# 23_PCIe.net
KiCad netlist of a schematic drawn in Altium Designer
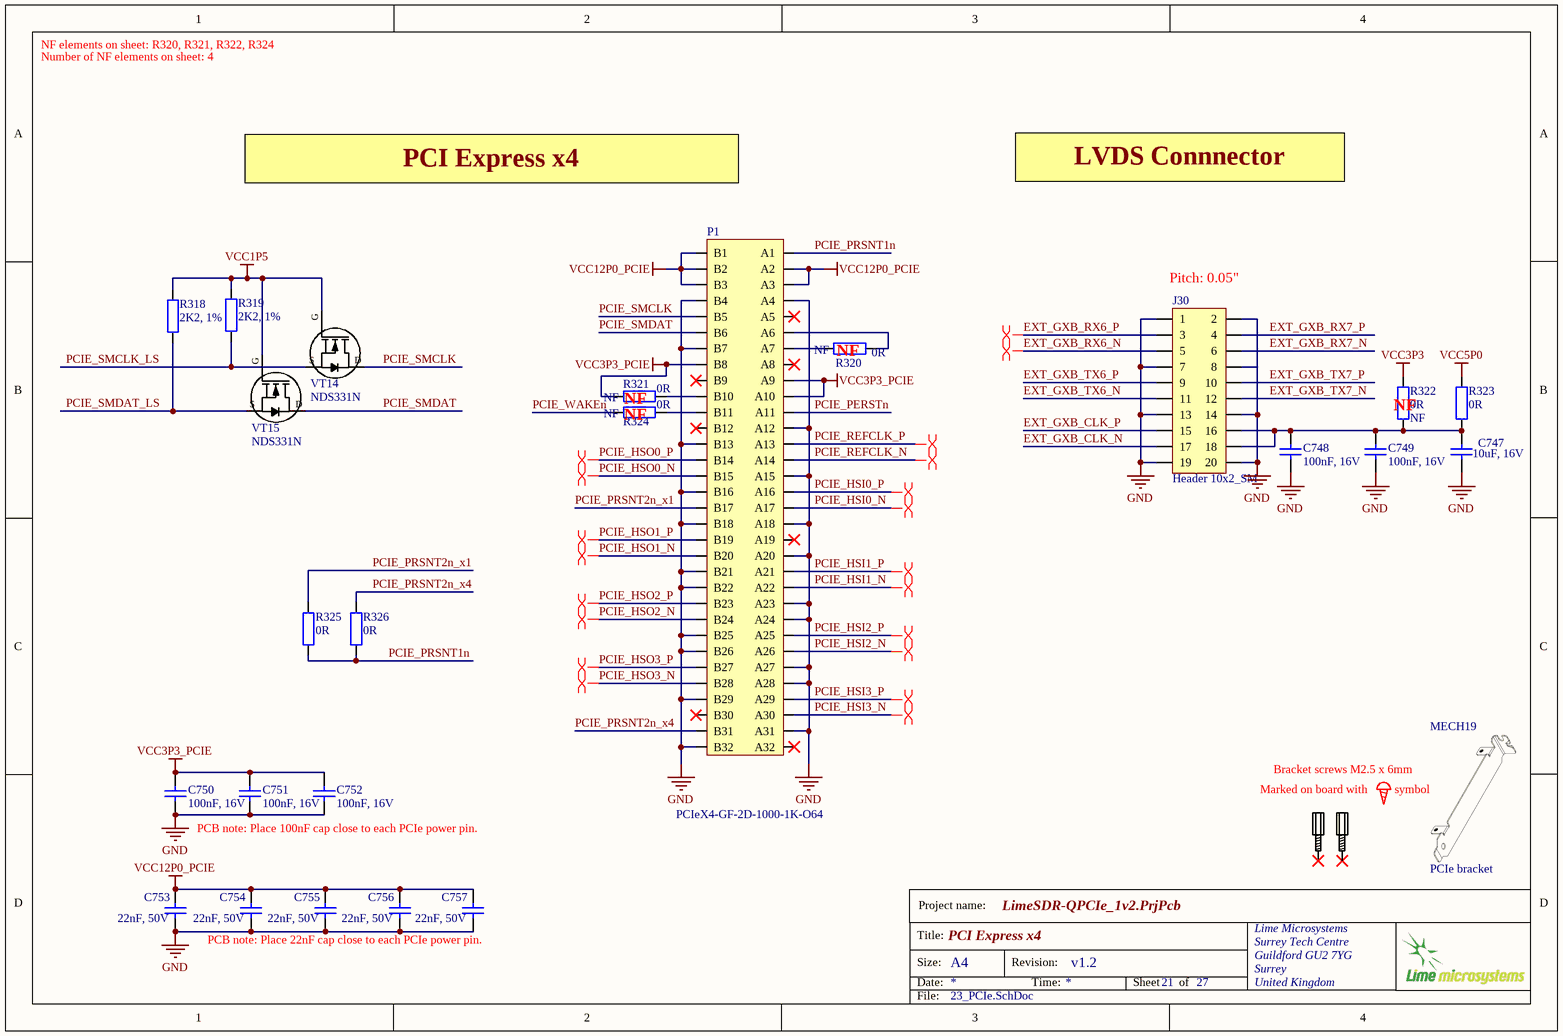
[diagram p0: 23_PCIe.SchDoc]

(export (version "E")
  (design (tool "Eeschema 10.0.6"))
  (components
    (comp (ref "C747")
      (value "10uF, 16V")
      (footprint "CAP0603")
      (fields (field (name "MANUFACTURER") "Yageo") (field (name "TOLERANCE") "±20%"))
      (libsource (lib "LimeMicroAltiumLib_schLib") (part "Cap_0603"))
    )
    (comp (ref "C748")
      (value "100nF, 16V")
      (footprint "CAP0402")
      (fields
        (field (name "TOLERANCE") "10 %")
        (field (name "MANUFACTURER") "Murata Electronics")
        (field (name "MANUFACTURER PART NUMBER") "GRM155R71C104KA88D")
      )
      (libsource (lib "LimeFPGAboard_schLib") (part "Cap_0603"))
    )
    (comp (ref "C749")
      (value "100nF, 16V")
      (footprint "CAP0402")
      (fields
        (field (name "TOLERANCE") "10 %")
        (field (name "MANUFACTURER") "Murata Electronics")
        (field (name "MANUFACTURER PART NUMBER") "GRM155R71C104KA88D")
      )
      (libsource (lib "LimeFPGAboard_schLib") (part "Cap_0603"))
    )
    (comp (ref "C750")
      (value "100nF, 16V")
      (footprint "CAP0402")
      (fields
        (field (name "TOLERANCE") "10 %")
        (field (name "MANUFACTURER") "Murata Electronics")
        (field (name "MANUFACTURER PART NUMBER") "GRM155R71C104KA88D")
      )
      (libsource (lib "LimeFPGAboard_schLib") (part "Cap_0603"))
    )
    (comp (ref "C751")
      (value "100nF, 16V")
      (footprint "CAP0402")
      (fields
        (field (name "TOLERANCE") "10 %")
        (field (name "MANUFACTURER") "Murata Electronics")
        (field (name "MANUFACTURER PART NUMBER") "GRM155R71C104KA88D")
      )
      (libsource (lib "LimeFPGAboard_schLib") (part "Cap_0603"))
    )
    (comp (ref "C752")
      (value "100nF, 16V")
      (footprint "CAP0402")
      (fields
        (field (name "TOLERANCE") "10 %")
        (field (name "MANUFACTURER") "Murata Electronics")
        (field (name "MANUFACTURER PART NUMBER") "GRM155R71C104KA88D")
      )
      (libsource (lib "LimeFPGAboard_schLib") (part "Cap_0603"))
    )
    (comp (ref "C753")
      (value "22nF, 50V")
      (footprint "CAP0402")
      (fields (field (name "TOLERANCE") "±10%") (field (name "MANUFACTURER") "Kemet"))
      (libsource (lib "LimeMicroAltiumLib_schLib") (part "Cap_0402"))
    )
    (comp (ref "C754")
      (value "22nF, 50V")
      (footprint "CAP0402")
      (fields (field (name "TOLERANCE") "±10%") (field (name "MANUFACTURER") "Kemet"))
      (libsource (lib "LimeMicroAltiumLib_schLib") (part "Cap_0402"))
    )
    (comp (ref "C755")
      (value "22nF, 50V")
      (footprint "CAP0402")
      (fields (field (name "TOLERANCE") "±10%") (field (name "MANUFACTURER") "Kemet"))
      (libsource (lib "LimeMicroAltiumLib_schLib") (part "Cap_0402"))
    )
    (comp (ref "C756")
      (value "22nF, 50V")
      (footprint "CAP0402")
      (fields (field (name "TOLERANCE") "±10%") (field (name "MANUFACTURER") "Kemet"))
      (libsource (lib "LimeMicroAltiumLib_schLib") (part "Cap_0402"))
    )
    (comp (ref "C757")
      (value "22nF, 50V")
      (footprint "CAP0402")
      (fields (field (name "TOLERANCE") "±10%") (field (name "MANUFACTURER") "Kemet"))
      (libsource (lib "LimeMicroAltiumLib_schLib") (part "Cap_0402"))
    )
    (comp (ref "J30")
      (value "Header 10x2_SM")
      (footprint "HEADER_10x2_SM_HALF_PITCH")
      (fields (field (name "MANUFACTURER") "Amphenol FCI"))
      (libsource (lib "LimeMicroAltiumLib_schLib") (part "Header 10x2_SM"))
    )
    (comp (ref "MECH19")
      (value "PCIe bracket")
      (footprint "PCIe_bracket")
      (fields (field (name "MANUFACTURER") "Keystone Electronics"))
      (libsource (lib "LimeMicroAltiumLib_schLib") (part "PCIe_bracket"))
    )
    (comp (ref "MECH20")
      (value "Spacer M3")
      (footprint "PCIe_bracket_screw_M2.5")
      (description "STANDOFF M/F MET 5MM HEX 10MM L")
      (fields (field (name "MANUFACTURER") "DURATOOL"))
      (libsource (lib "LimeMicroAltiumLib_schLib") (part "STANDOFF_M-F_THREADED_M3x8x10mm_HEX_5mm dia"))
    )
    (comp (ref "MECH21")
      (value "Spacer M3")
      (footprint "PCIe_bracket_screw_M2.5")
      (description "STANDOFF M/F MET 5MM HEX 10MM L")
      (fields (field (name "MANUFACTURER") "DURATOOL"))
      (libsource (lib "LimeMicroAltiumLib_schLib") (part "STANDOFF_M-F_THREADED_M3x8x10mm_HEX_5mm dia"))
    )
    (comp (ref "P1")
      (value "PCIeX4-GF-2D-1000-1K-O64")
      (footprint "PCIeX4-GF-2D-1000-1K-O64")
      (libsource (lib "LimeMicroAltiumLib_schLib") (part "PCIeX4-GF-2D-1000-1K-O64"))
    )
    (comp (ref "R318")
      (value "2K2, 1%")
      (footprint "RES0402")
      (fields (field (name "TOLERANCE") "±1%"))
      (libsource (lib "LimeFPGAboard_schLib") (part "Res_0402"))
    )
    (comp (ref "R319")
      (value "2K2, 1%")
      (footprint "RES0402")
      (fields (field (name "TOLERANCE") "±1%"))
      (libsource (lib "LimeFPGAboard_schLib") (part "Res_0402"))
    )
    (comp (ref "R320")
      (value "0R")
      (footprint "RES0402")
      (fields (field (name "MANUFACTURER") "Yageo") (field (name "ASSEMBLY INFO") "NF"))
      (libsource (lib "LimeFPGAboard_schLib") (part "Res_0402"))
    )
    (comp (ref "R321")
      (value "0R")
      (footprint "RES0402")
      (fields (field (name "MANUFACTURER") "Yageo") (field (name "ASSEMBLY INFO") "NF"))
      (libsource (lib "LimeFPGAboard_schLib") (part "Res_0402"))
    )
    (comp (ref "R322")
      (value "0R")
      (footprint "RES0402")
      (fields
        (field (name "ASSEMBLY INFO") "NF")
        (field (name "MANUFACTURER") "Yageo")
        (field (name "TOLERANCE") "Jumper")
      )
      (libsource (lib "LimeMicroAltiumLib_schLib") (part "Res_0402"))
    )
    (comp (ref "R323")
      (value "0R")
      (footprint "RES0402")
      (fields (field (name "MANUFACTURER") "Yageo") (field (name "TOLERANCE") "Jumper"))
      (libsource (lib "LimeMicroAltiumLib_schLib") (part "Res_0402"))
    )
    (comp (ref "R324")
      (value "0R")
      (footprint "RES0402")
      (fields (field (name "MANUFACTURER") "Yageo") (field (name "ASSEMBLY INFO") "NF"))
      (libsource (lib "LimeFPGAboard_schLib") (part "Res_0402"))
    )
    (comp (ref "R325")
      (value "0R")
      (footprint "RES0402")
      (fields (field (name "MANUFACTURER") "Yageo"))
      (libsource (lib "LimeFPGAboard_schLib") (part "Res_0402"))
    )
    (comp (ref "R326")
      (value "0R")
      (footprint "RES0402")
      (fields (field (name "MANUFACTURER") "Yageo"))
      (libsource (lib "LimeFPGAboard_schLib") (part "Res_0402"))
    )
    (comp (ref "VT14")
      (value "NDS331N")
      (footprint "SOT23-3")
      (fields (field (name "MANUFACTURER") "Fairchild Semiconductor"))
      (libsource (lib "LimeFPGAboard_schLib") (part "NDS331N"))
    )
    (comp (ref "VT15")
      (value "NDS331N")
      (footprint "SOT23-3")
      (fields (field (name "MANUFACTURER") "Fairchild Semiconductor"))
      (libsource (lib "LimeFPGAboard_schLib") (part "NDS331N"))
    )
  )
  (nets
    (net (code "1") (name "/EXT_GXB_CLK_N") (class "Default")
      (node (ref "J30") (pin "17") (pinfunction "17_17") (pintype "passive"))
    )
    (net (code "2") (name "/EXT_GXB_CLK_P") (class "Default")
      (node (ref "J30") (pin "15") (pinfunction "15_15") (pintype "passive"))
    )
    (net (code "3") (name "/EXT_GXB_RX6_N") (class "Default")
      (node (ref "J30") (pin "5") (pinfunction "5_5") (pintype "passive"))
    )
    (net (code "4") (name "/EXT_GXB_RX6_P") (class "Default")
      (node (ref "J30") (pin "3") (pinfunction "3_3") (pintype "passive"))
    )
    (net (code "5") (name "/EXT_GXB_RX7_N") (class "Default")
      (node (ref "J30") (pin "6") (pinfunction "6_6") (pintype "passive"))
    )
    (net (code "6") (name "/EXT_GXB_RX7_P") (class "Default")
      (node (ref "J30") (pin "4") (pinfunction "4_4") (pintype "passive"))
    )
    (net (code "7") (name "/EXT_GXB_TX6_N") (class "Default")
      (node (ref "J30") (pin "11") (pinfunction "11_11") (pintype "passive"))
    )
    (net (code "8") (name "/EXT_GXB_TX6_P") (class "Default")
      (node (ref "J30") (pin "9") (pinfunction "9_9") (pintype "passive"))
    )
    (net (code "9") (name "/EXT_GXB_TX7_N") (class "Default")
      (node (ref "J30") (pin "12") (pinfunction "12_12") (pintype "passive"))
    )
    (net (code "10") (name "/EXT_GXB_TX7_P") (class "Default")
      (node (ref "J30") (pin "10") (pinfunction "10_10") (pintype "passive"))
    )
    (net (code "11") (name "/PCIE_HSI0_N") (class "Default")
      (node (ref "P1") (pin "A17") (pinfunction "A17_A17") (pintype "passive"))
    )
    (net (code "12") (name "/PCIE_HSI0_P") (class "Default")
      (node (ref "P1") (pin "A16") (pinfunction "A16_A16") (pintype "passive"))
    )
    (net (code "13") (name "/PCIE_HSI1_N") (class "Default")
      (node (ref "P1") (pin "A22") (pinfunction "A22_A22") (pintype "passive"))
    )
    (net (code "14") (name "/PCIE_HSI1_P") (class "Default")
      (node (ref "P1") (pin "A21") (pinfunction "A21_A21") (pintype "passive"))
    )
    (net (code "15") (name "/PCIE_HSI2_N") (class "Default")
      (node (ref "P1") (pin "A26") (pinfunction "A26_A26") (pintype "passive"))
    )
    (net (code "16") (name "/PCIE_HSI2_P") (class "Default")
      (node (ref "P1") (pin "A25") (pinfunction "A25_A25") (pintype "passive"))
    )
    (net (code "17") (name "/PCIE_HSI3_N") (class "Default")
      (node (ref "P1") (pin "A30") (pinfunction "A30_A30") (pintype "passive"))
    )
    (net (code "18") (name "/PCIE_HSI3_P") (class "Default")
      (node (ref "P1") (pin "A29") (pinfunction "A29_A29") (pintype "passive"))
    )
    (net (code "19") (name "/PCIE_HSO0_N") (class "Default")
      (node (ref "P1") (pin "B15") (pinfunction "B15_B15") (pintype "passive"))
    )
    (net (code "20") (name "/PCIE_HSO0_P") (class "Default")
      (node (ref "P1") (pin "B14") (pinfunction "B14_B14") (pintype "passive"))
    )
    (net (code "21") (name "/PCIE_HSO1_N") (class "Default")
      (node (ref "P1") (pin "B20") (pinfunction "B20_B20") (pintype "passive"))
    )
    (net (code "22") (name "/PCIE_HSO1_P") (class "Default")
      (node (ref "P1") (pin "B19") (pinfunction "B19_B19") (pintype "passive"))
    )
    (net (code "23") (name "/PCIE_HSO2_N") (class "Default")
      (node (ref "P1") (pin "B24") (pinfunction "B24_B24") (pintype "passive"))
    )
    (net (code "24") (name "/PCIE_HSO2_P") (class "Default")
      (node (ref "P1") (pin "B23") (pinfunction "B23_B23") (pintype "passive"))
    )
    (net (code "25") (name "/PCIE_HSO3_N") (class "Default")
      (node (ref "P1") (pin "B28") (pinfunction "B28_B28") (pintype "passive"))
    )
    (net (code "26") (name "/PCIE_HSO3_P") (class "Default")
      (node (ref "P1") (pin "B27") (pinfunction "B27_B27") (pintype "passive"))
    )
    (net (code "27") (name "/PCIE_PERSTn") (class "Default")
      (node (ref "P1") (pin "A11") (pinfunction "A11_A11") (pintype "passive"))
    )
    (net (code "28") (name "/PCIE_PRSNT1n") (class "Default")
      (node (ref "P1") (pin "A1") (pinfunction "A1_A1") (pintype "passive"))
      (node (ref "R325") (pin "1") (pinfunction "1_1") (pintype "passive"))
      (node (ref "R326") (pin "1") (pinfunction "1_1") (pintype "passive"))
    )
    (net (code "29") (name "/PCIE_PRSNT2n_x1") (class "Default")
      (node (ref "P1") (pin "B17") (pinfunction "B17_B17") (pintype "passive"))
      (node (ref "R325") (pin "2") (pinfunction "2_2") (pintype "passive"))
    )
    (net (code "30") (name "/PCIE_PRSNT2n_x4") (class "Default")
      (node (ref "P1") (pin "B31") (pinfunction "B31_B31") (pintype "passive"))
      (node (ref "R326") (pin "2") (pinfunction "2_2") (pintype "passive"))
    )
    (net (code "31") (name "/PCIE_REFCLK_N") (class "Default")
      (node (ref "P1") (pin "A14") (pinfunction "A14_A14") (pintype "passive"))
    )
    (net (code "32") (name "/PCIE_REFCLK_P") (class "Default")
      (node (ref "P1") (pin "A13") (pinfunction "A13_A13") (pintype "passive"))
    )
    (net (code "33") (name "/PCIE_SMCLK") (class "Default")
      (node (ref "P1") (pin "B5") (pinfunction "B5_B5") (pintype "passive"))
      (node (ref "VT14") (pin "D") (pinfunction "D_D") (pintype "passive"))
    )
    (net (code "34") (name "/PCIE_SMCLK_LS") (class "Default")
      (node (ref "R319") (pin "2") (pinfunction "2_2") (pintype "passive"))
      (node (ref "VT14") (pin "S") (pinfunction "S_S") (pintype "passive"))
    )
    (net (code "35") (name "/PCIE_SMDAT") (class "Default")
      (node (ref "P1") (pin "B6") (pinfunction "B6_B6") (pintype "passive"))
      (node (ref "VT15") (pin "D") (pinfunction "D_D") (pintype "passive"))
    )
    (net (code "36") (name "/PCIE_SMDAT_LS") (class "Default")
      (node (ref "R318") (pin "2") (pinfunction "2_2") (pintype "passive"))
      (node (ref "VT15") (pin "S") (pinfunction "S_S") (pintype "passive"))
    )
    (net (code "37") (name "/PCIE_WAKEn") (class "Default")
      (node (ref "R324") (pin "1") (pinfunction "1_1") (pintype "passive"))
    )
    (net (code "38") (name "GND") (class "Default")
      (node (ref "C747") (pin "1") (pinfunction "1_1") (pintype "passive"))
      (node (ref "C748") (pin "2") (pinfunction "2_2") (pintype "passive"))
      (node (ref "C749") (pin "2") (pinfunction "2_2") (pintype "passive"))
      (node (ref "C750") (pin "2") (pinfunction "2_2") (pintype "passive"))
      (node (ref "C751") (pin "2") (pinfunction "2_2") (pintype "passive"))
      (node (ref "C752") (pin "2") (pinfunction "2_2") (pintype "passive"))
      (node (ref "C753") (pin "2") (pinfunction "2_2") (pintype "passive"))
      (node (ref "C754") (pin "2") (pinfunction "2_2") (pintype "passive"))
      (node (ref "C755") (pin "2") (pinfunction "2_2") (pintype "passive"))
      (node (ref "C756") (pin "2") (pinfunction "2_2") (pintype "passive"))
      (node (ref "C757") (pin "2") (pinfunction "2_2") (pintype "passive"))
      (node (ref "J30") (pin "1") (pinfunction "1_1") (pintype "passive"))
      (node (ref "J30") (pin "13") (pinfunction "13_13") (pintype "passive"))
      (node (ref "J30") (pin "14") (pinfunction "14_14") (pintype "passive"))
      (node (ref "J30") (pin "19") (pinfunction "19_19") (pintype "passive"))
      (node (ref "J30") (pin "2") (pinfunction "2_2") (pintype "passive"))
      (node (ref "J30") (pin "20") (pinfunction "20_20") (pintype "passive"))
      (node (ref "J30") (pin "7") (pinfunction "7_7") (pintype "passive"))
      (node (ref "J30") (pin "8") (pinfunction "8_8") (pintype "passive"))
      (node (ref "P1") (pin "A12") (pinfunction "A12_A12") (pintype "passive"))
      (node (ref "P1") (pin "A15") (pinfunction "A15_A15") (pintype "passive"))
      (node (ref "P1") (pin "A18") (pinfunction "A18_A18") (pintype "passive"))
      (node (ref "P1") (pin "A20") (pinfunction "A20_A20") (pintype "passive"))
      (node (ref "P1") (pin "A23") (pinfunction "A23_A23") (pintype "passive"))
      (node (ref "P1") (pin "A24") (pinfunction "A24_A24") (pintype "passive"))
      (node (ref "P1") (pin "A27") (pinfunction "A27_A27") (pintype "passive"))
      (node (ref "P1") (pin "A28") (pinfunction "A28_A28") (pintype "passive"))
      (node (ref "P1") (pin "A31") (pinfunction "A31_A31") (pintype "passive"))
      (node (ref "P1") (pin "A4") (pinfunction "A4_A4") (pintype "passive"))
      (node (ref "P1") (pin "B13") (pinfunction "B13_B13") (pintype "passive"))
      (node (ref "P1") (pin "B16") (pinfunction "B16_B16") (pintype "passive"))
      (node (ref "P1") (pin "B18") (pinfunction "B18_B18") (pintype "passive"))
      (node (ref "P1") (pin "B21") (pinfunction "B21_B21") (pintype "passive"))
      (node (ref "P1") (pin "B22") (pinfunction "B22_B22") (pintype "passive"))
      (node (ref "P1") (pin "B25") (pinfunction "B25_B25") (pintype "passive"))
      (node (ref "P1") (pin "B26") (pinfunction "B26_B26") (pintype "passive"))
      (node (ref "P1") (pin "B29") (pinfunction "B29_B29") (pintype "passive"))
      (node (ref "P1") (pin "B32") (pinfunction "B32_B32") (pintype "passive"))
      (node (ref "P1") (pin "B4") (pinfunction "B4_B4") (pintype "passive"))
      (node (ref "P1") (pin "B7") (pinfunction "B7_B7") (pintype "passive"))
    )
    (net (code "39") (name "Net-(C747-Pad2)") (class "Default")
      (node (ref "C747") (pin "2") (pinfunction "2_2") (pintype "passive"))
      (node (ref "C748") (pin "1") (pinfunction "1_1") (pintype "passive"))
      (node (ref "C749") (pin "1") (pinfunction "1_1") (pintype "passive"))
      (node (ref "J30") (pin "16") (pinfunction "16_16") (pintype "passive"))
      (node (ref "J30") (pin "18") (pinfunction "18_18") (pintype "passive"))
      (node (ref "R322") (pin "2") (pinfunction "2_2") (pintype "passive"))
      (node (ref "R323") (pin "2") (pinfunction "2_2") (pintype "passive"))
    )
    (net (code "40") (name "Net-(P1-PadA6)") (class "Default")
      (node (ref "P1") (pin "A6") (pinfunction "A6_A6") (pintype "passive"))
      (node (ref "R320") (pin "2") (pinfunction "2_2") (pintype "passive"))
    )
    (net (code "41") (name "Net-(P1-PadA7)") (class "Default")
      (node (ref "P1") (pin "A7") (pinfunction "A7_A7") (pintype "passive"))
      (node (ref "R320") (pin "1") (pinfunction "1_1") (pintype "passive"))
    )
    (net (code "42") (name "Net-(P1-PadB10)") (class "Default")
      (node (ref "P1") (pin "B10") (pinfunction "B10_B10") (pintype "passive"))
      (node (ref "R321") (pin "2") (pinfunction "2_2") (pintype "passive"))
    )
    (net (code "43") (name "Net-(P1-PadB11)") (class "Default")
      (node (ref "P1") (pin "B11") (pinfunction "B11_B11") (pintype "passive"))
      (node (ref "R324") (pin "2") (pinfunction "2_2") (pintype "passive"))
    )
    (net (code "44") (name "VCC1P5") (class "Default")
      (node (ref "R318") (pin "1") (pinfunction "1_1") (pintype "passive"))
      (node (ref "R319") (pin "1") (pinfunction "1_1") (pintype "passive"))
      (node (ref "VT14") (pin "G") (pinfunction "G_G") (pintype "passive"))
      (node (ref "VT15") (pin "G") (pinfunction "G_G") (pintype "passive"))
    )
    (net (code "45") (name "VCC3P3") (class "Default")
      (node (ref "R322") (pin "1") (pinfunction "1_1") (pintype "passive"))
    )
    (net (code "46") (name "VCC3P3_PCIE") (class "Default")
      (node (ref "C750") (pin "1") (pinfunction "1_1") (pintype "passive"))
      (node (ref "C751") (pin "1") (pinfunction "1_1") (pintype "passive"))
      (node (ref "C752") (pin "1") (pinfunction "1_1") (pintype "passive"))
      (node (ref "P1") (pin "A10") (pinfunction "A10_A10") (pintype "passive"))
      (node (ref "P1") (pin "A9") (pinfunction "A9_A9") (pintype "passive"))
      (node (ref "P1") (pin "B8") (pinfunction "B8_B8") (pintype "passive"))
      (node (ref "R321") (pin "1") (pinfunction "1_1") (pintype "passive"))
    )
    (net (code "47") (name "VCC5P0") (class "Default")
      (node (ref "R323") (pin "1") (pinfunction "1_1") (pintype "passive"))
    )
    (net (code "48") (name "VCC12P0_PCIE") (class "Default")
      (node (ref "C753") (pin "1") (pinfunction "1_1") (pintype "passive"))
      (node (ref "C754") (pin "1") (pinfunction "1_1") (pintype "passive"))
      (node (ref "C755") (pin "1") (pinfunction "1_1") (pintype "passive"))
      (node (ref "C756") (pin "1") (pinfunction "1_1") (pintype "passive"))
      (node (ref "C757") (pin "1") (pinfunction "1_1") (pintype "passive"))
      (node (ref "P1") (pin "A2") (pinfunction "A2_A2") (pintype "passive"))
      (node (ref "P1") (pin "A3") (pinfunction "A3_A3") (pintype "passive"))
      (node (ref "P1") (pin "B1") (pinfunction "B1_B1") (pintype "passive"))
      (node (ref "P1") (pin "B2") (pinfunction "B2_B2") (pintype "passive"))
      (node (ref "P1") (pin "B3") (pinfunction "B3_B3") (pintype "passive"))
    )
    (net (code "49") (name "unconnected-(MECH20-PadMH1)") (class "Default")
      (node (ref "MECH20") (pin "MH1") (pinfunction "MH1_MH1") (pintype "passive+no_connect"))
    )
    (net (code "50") (name "unconnected-(MECH21-PadMH1)") (class "Default")
      (node (ref "MECH21") (pin "MH1") (pinfunction "MH1_MH1") (pintype "passive+no_connect"))
    )
    (net (code "51") (name "unconnected-(P1-PadA5)") (class "Default")
      (node (ref "P1") (pin "A5") (pinfunction "A5_A5") (pintype "passive+no_connect"))
    )
    (net (code "52") (name "unconnected-(P1-PadA8)") (class "Default")
      (node (ref "P1") (pin "A8") (pinfunction "A8_A8") (pintype "passive+no_connect"))
    )
    (net (code "53") (name "unconnected-(P1-PadA19)") (class "Default")
      (node (ref "P1") (pin "A19") (pinfunction "A19_A19") (pintype "passive+no_connect"))
    )
    (net (code "54") (name "unconnected-(P1-PadA32)") (class "Default")
      (node (ref "P1") (pin "A32") (pinfunction "A32_A32") (pintype "passive+no_connect"))
    )
    (net (code "55") (name "unconnected-(P1-PadB9)") (class "Default")
      (node (ref "P1") (pin "B9") (pinfunction "B9_B9") (pintype "passive+no_connect"))
    )
    (net (code "56") (name "unconnected-(P1-PadB12)") (class "Default")
      (node (ref "P1") (pin "B12") (pinfunction "B12_B12") (pintype "passive+no_connect"))
    )
    (net (code "57") (name "unconnected-(P1-PadB30)") (class "Default")
      (node (ref "P1") (pin "B30") (pinfunction "B30_B30") (pintype "passive+no_connect"))
    )
  )
)
